# ThousandSunny.net
KiCad netlist of a schematic drawn in EAGLE
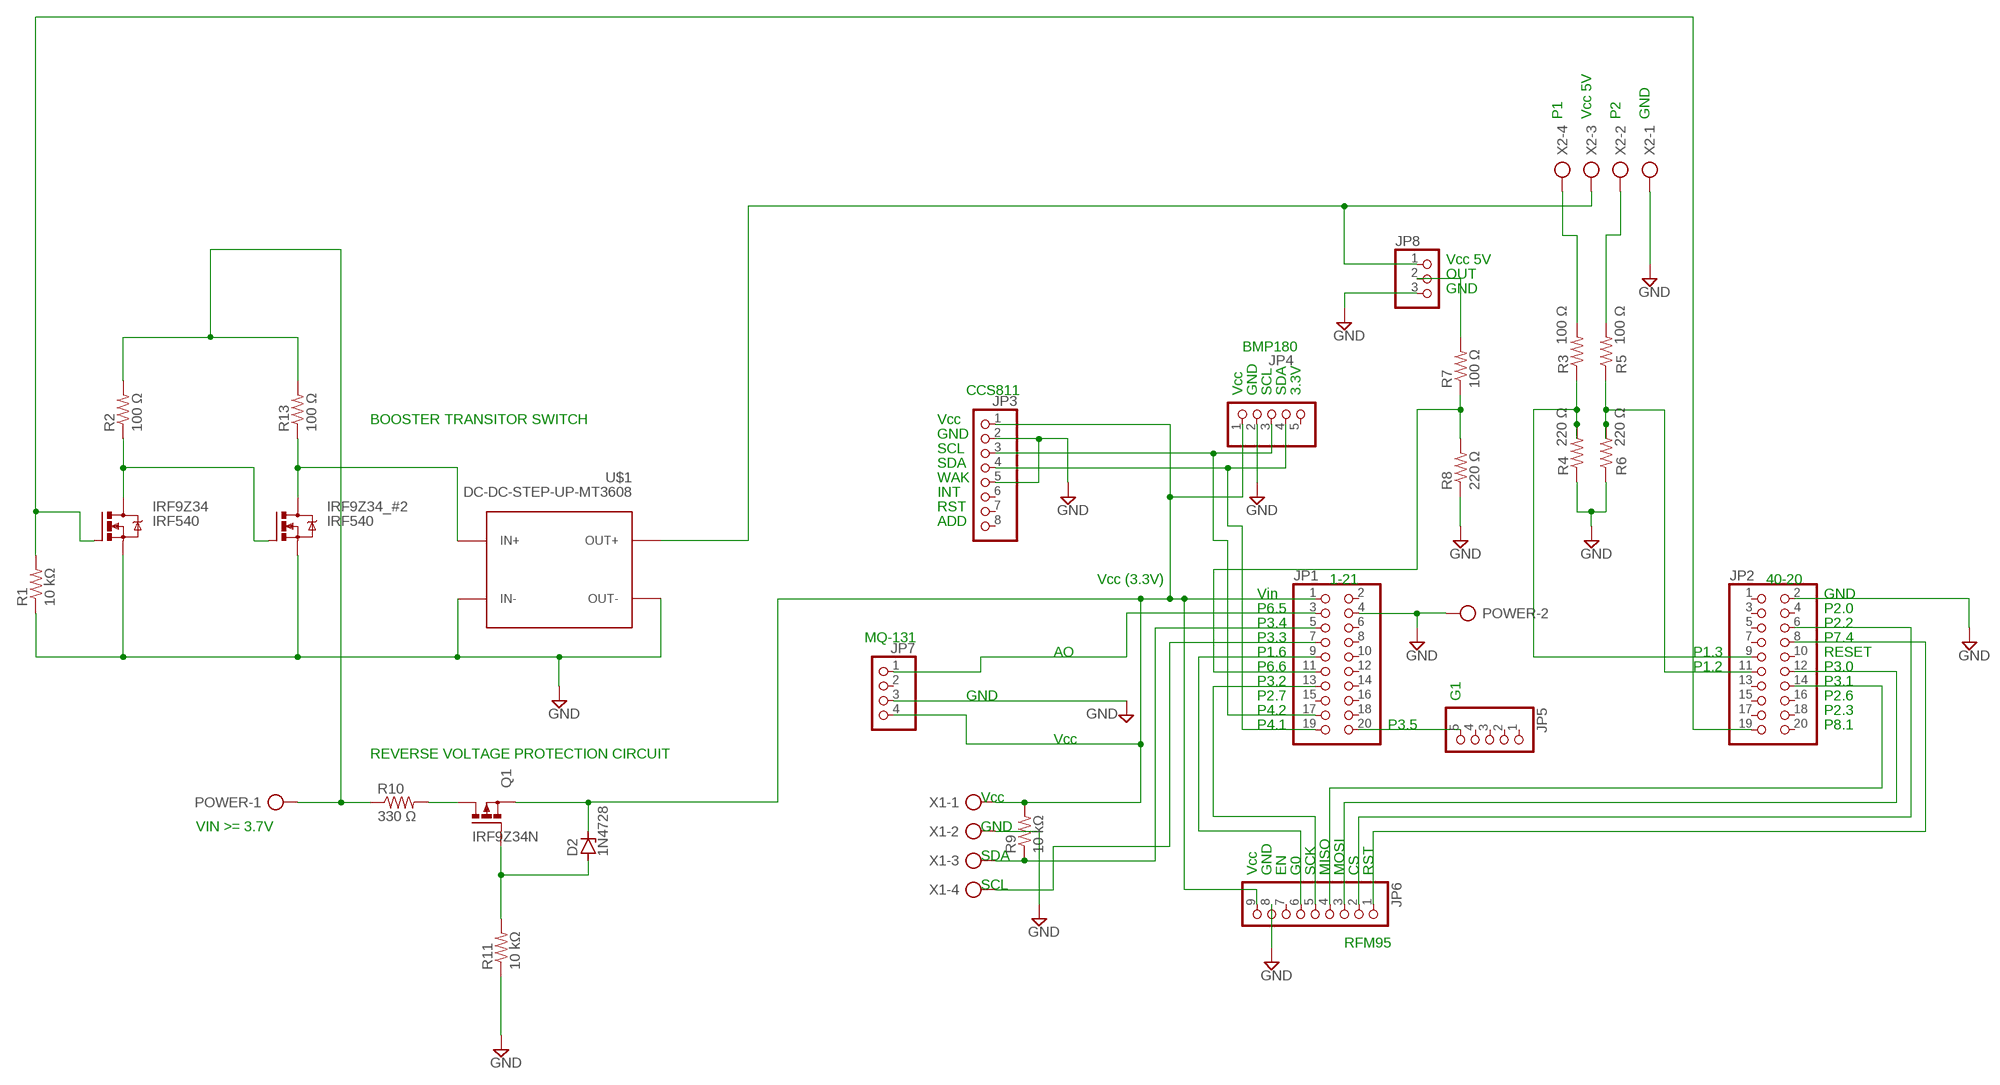
[diagram p0: schematic, sheet 1]

(export (version "E")
  (design (tool "Eeschema 10.0.6"))
  (components
    (comp (ref "D2")
      (value "1N4728")
      (footprint "eagle-import:DO41Z10")
      (libsource (lib "eagle-import") (part "1N4728"))
    )
    (comp (ref "IRF9Z34")
      (value "IRF540")
      (footprint "eagle-import:TO220BV")
      (libsource (lib "eagle-import") (part "IRF540"))
    )
    (comp (ref "IRF9Z34_#2")
      (value "IRF540")
      (footprint "eagle-import:TO220BV")
      (libsource (lib "eagle-import") (part "IRF540"))
    )
    (comp (ref "JP1")
      (value "PINHD-2X10")
      (footprint "eagle-import:2X10")
      (libsource (lib "eagle-import") (part "PINHD-2X10"))
    )
    (comp (ref "JP2")
      (value "PINHD-2X10")
      (footprint "eagle-import:2X10")
      (libsource (lib "eagle-import") (part "PINHD-2X10"))
    )
    (comp (ref "JP3")
      (value "PINHD-1X8")
      (footprint "eagle-import:1X08")
      (libsource (lib "eagle-import") (part "PINHD-1X8"))
    )
    (comp (ref "JP4")
      (value "PINHD-1X5")
      (footprint "eagle-import:1X05")
      (libsource (lib "eagle-import") (part "PINHD-1X5"))
    )
    (comp (ref "JP5")
      (value "PINHD-1X5")
      (footprint "eagle-import:1X05")
      (libsource (lib "eagle-import") (part "PINHD-1X5"))
    )
    (comp (ref "JP6")
      (value "PINHD-1X9")
      (footprint "eagle-import:1X09")
      (libsource (lib "eagle-import") (part "PINHD-1X9"))
    )
    (comp (ref "JP7")
      (value "PINHD-1X4")
      (footprint "eagle-import:1X04")
      (libsource (lib "eagle-import") (part "PINHD-1X4"))
    )
    (comp (ref "JP8")
      (value "PINHD-1X3")
      (footprint "eagle-import:1X03")
      (libsource (lib "eagle-import") (part "PINHD-1X3"))
    )
    (comp (ref "POWER")
      (value "AK300/2")
      (footprint "eagle-import:AK300_2")
      (libsource (lib "eagle-import") (part "AK300/2"))
    )
    (comp (ref "Q1")
      (value "IRF9Z34N")
      (footprint "eagle-import:TO220BV")
      (libsource (lib "eagle-import") (part "PMOSFET_PTO220BV"))
    )
    (comp (ref "R1")
      (value "10 kΩ")
      (footprint "eagle-import:0204_7")
      (libsource (lib "eagle-import") (part "R-US_0204/7"))
    )
    (comp (ref "R2")
      (value "100 Ω")
      (footprint "eagle-import:0204_7")
      (libsource (lib "eagle-import") (part "R-US_0204/7"))
    )
    (comp (ref "R3")
      (value "100 Ω")
      (footprint "eagle-import:0204_7")
      (libsource (lib "eagle-import") (part "R-US_0204/7"))
    )
    (comp (ref "R4")
      (value "220 Ω")
      (footprint "eagle-import:0204_7")
      (libsource (lib "eagle-import") (part "R-US_0204/7"))
    )
    (comp (ref "R5")
      (value "100 Ω")
      (footprint "eagle-import:0204_7")
      (libsource (lib "eagle-import") (part "R-US_0204/7"))
    )
    (comp (ref "R6")
      (value "220 Ω")
      (footprint "eagle-import:0204_7")
      (libsource (lib "eagle-import") (part "R-US_0204/7"))
    )
    (comp (ref "R7")
      (value "100 Ω")
      (footprint "eagle-import:0204_7")
      (libsource (lib "eagle-import") (part "R-US_0204/7"))
    )
    (comp (ref "R8")
      (value "220 Ω")
      (footprint "eagle-import:0204_7")
      (libsource (lib "eagle-import") (part "R-US_0204/7"))
    )
    (comp (ref "R9")
      (value "10 kΩ")
      (footprint "eagle-import:0204_7")
      (libsource (lib "eagle-import") (part "R-US_0204/7"))
    )
    (comp (ref "R10")
      (value "330 Ω")
      (footprint "eagle-import:0204_7")
      (libsource (lib "eagle-import") (part "R-US_0204/7"))
    )
    (comp (ref "R11")
      (value "10 kΩ")
      (footprint "eagle-import:0204_7")
      (libsource (lib "eagle-import") (part "R-US_0204/7"))
    )
    (comp (ref "R13")
      (value "100 Ω")
      (footprint "eagle-import:0204_7")
      (libsource (lib "eagle-import") (part "R-US_0204/7"))
    )
    (comp (ref "U$1")
      (value "DC-DC-STEP-UP-MT3608")
      (footprint "eagle-import:DC-DC-STEP-UP-MT3608")
      (libsource (lib "eagle-import") (part "DC-DC-STEP-UP-MT3608"))
    )
    (comp (ref "X1")
      (value "AK300/4")
      (footprint "eagle-import:AK300_4")
      (libsource (lib "eagle-import") (part "AK300/4"))
    )
    (comp (ref "X2")
      (value "AK300/4")
      (footprint "eagle-import:AK300_4")
      (libsource (lib "eagle-import") (part "AK300/4"))
    )
  )
  (nets
    (net (code "1") (name "GND") (class "Default")
      (node (ref "IRF9Z34") (pin "S") (pinfunction "S_S") (pintype "passive"))
      (node (ref "IRF9Z34_#2") (pin "S") (pinfunction "S_S") (pintype "passive"))
      (node (ref "JP1") (pin "4") (pinfunction "4_4") (pintype "passive"))
      (node (ref "JP2") (pin "2") (pinfunction "2_2") (pintype "passive"))
      (node (ref "JP3") (pin "2") (pinfunction "2_2") (pintype "passive"))
      (node (ref "JP3") (pin "5") (pinfunction "5_5") (pintype "passive"))
      (node (ref "JP4") (pin "2") (pinfunction "2_2") (pintype "passive"))
      (node (ref "JP6") (pin "8") (pinfunction "8_8") (pintype "passive"))
      (node (ref "JP7") (pin "3") (pinfunction "3_3") (pintype "passive"))
      (node (ref "JP8") (pin "3") (pinfunction "3_3") (pintype "passive"))
      (node (ref "POWER") (pin "2") (pinfunction "KL_2") (pintype "passive"))
      (node (ref "R1") (pin "1") (pinfunction "1_1") (pintype "passive"))
      (node (ref "R11") (pin "1") (pinfunction "1_1") (pintype "passive"))
      (node (ref "R4") (pin "1") (pinfunction "1_1") (pintype "passive"))
      (node (ref "R6") (pin "1") (pinfunction "1_1") (pintype "passive"))
      (node (ref "R8") (pin "1") (pinfunction "1_1") (pintype "passive"))
      (node (ref "U$1") (pin "IN-") (pinfunction "IN-_IN-") (pintype "bidirectional"))
      (node (ref "U$1") (pin "OUT-") (pinfunction "OUT-_OUT-") (pintype "bidirectional"))
      (node (ref "X1") (pin "2") (pinfunction "KL_2") (pintype "passive"))
      (node (ref "X2") (pin "1") (pinfunction "KL_1") (pintype "passive"))
    )
    (net (code "2") (name "Net-(D2-PadA)") (class "Default")
      (node (ref "D2") (pin "A") (pinfunction "A_A") (pintype "passive"))
      (node (ref "Q1") (pin "G") (pinfunction "G_G") (pintype "passive"))
      (node (ref "R11") (pin "2") (pinfunction "2_2") (pintype "passive"))
    )
    (net (code "3") (name "Net-(IRF9Z34-PadD)") (class "Default")
      (node (ref "IRF9Z34") (pin "D") (pinfunction "D_D") (pintype "passive"))
      (node (ref "IRF9Z34_#2") (pin "G") (pinfunction "G_G") (pintype "passive"))
      (node (ref "R2") (pin "1") (pinfunction "1_1") (pintype "passive"))
    )
    (net (code "4") (name "Net-(IRF9Z34-PadG)") (class "Default")
      (node (ref "IRF9Z34") (pin "G") (pinfunction "G_G") (pintype "passive"))
      (node (ref "JP2") (pin "19") (pinfunction "19_19") (pintype "passive"))
      (node (ref "R1") (pin "2") (pinfunction "2_2") (pintype "passive"))
    )
    (net (code "5") (name "Net-(IRF9Z34_#2-PadD)") (class "Default")
      (node (ref "IRF9Z34_#2") (pin "D") (pinfunction "D_D") (pintype "passive"))
      (node (ref "R13") (pin "1") (pinfunction "1_1") (pintype "passive"))
      (node (ref "U$1") (pin "IN+") (pinfunction "IN+_IN+") (pintype "bidirectional"))
    )
    (net (code "6") (name "Net-(JP1-Pad3)") (class "Default")
      (node (ref "JP1") (pin "3") (pinfunction "3_3") (pintype "passive"))
      (node (ref "JP7") (pin "1") (pinfunction "1_1") (pintype "passive"))
    )
    (net (code "7") (name "Net-(JP1-Pad9)") (class "Default")
      (node (ref "JP1") (pin "9") (pinfunction "9_9") (pintype "passive"))
      (node (ref "JP6") (pin "6") (pinfunction "6_6") (pintype "passive"))
    )
    (net (code "8") (name "Net-(JP1-Pad11)") (class "Default")
      (node (ref "JP1") (pin "11") (pinfunction "11_11") (pintype "passive"))
      (node (ref "R7") (pin "1") (pinfunction "1_1") (pintype "passive"))
      (node (ref "R8") (pin "2") (pinfunction "2_2") (pintype "passive"))
    )
    (net (code "9") (name "Net-(JP1-Pad13)") (class "Default")
      (node (ref "JP1") (pin "13") (pinfunction "13_13") (pintype "passive"))
      (node (ref "JP6") (pin "5") (pinfunction "5_5") (pintype "passive"))
    )
    (net (code "10") (name "Net-(JP1-Pad17)") (class "Default")
      (node (ref "JP1") (pin "17") (pinfunction "17_17") (pintype "passive"))
      (node (ref "JP3") (pin "3") (pinfunction "3_3") (pintype "passive"))
      (node (ref "JP4") (pin "3") (pinfunction "3_3") (pintype "passive"))
    )
    (net (code "11") (name "Net-(JP1-Pad19)") (class "Default")
      (node (ref "JP1") (pin "19") (pinfunction "19_19") (pintype "passive"))
      (node (ref "JP3") (pin "4") (pinfunction "4_4") (pintype "passive"))
      (node (ref "JP4") (pin "4") (pinfunction "4_4") (pintype "passive"))
    )
    (net (code "12") (name "Net-(JP1-Pad20)") (class "Default")
      (node (ref "JP1") (pin "20") (pinfunction "20_20") (pintype "passive"))
      (node (ref "JP5") (pin "5") (pinfunction "5_5") (pintype "passive"))
    )
    (net (code "13") (name "Net-(JP2-Pad6)") (class "Default")
      (node (ref "JP2") (pin "6") (pinfunction "6_6") (pintype "passive"))
      (node (ref "JP6") (pin "2") (pinfunction "2_2") (pintype "passive"))
    )
    (net (code "14") (name "Net-(JP2-Pad8)") (class "Default")
      (node (ref "JP2") (pin "8") (pinfunction "8_8") (pintype "passive"))
      (node (ref "JP6") (pin "1") (pinfunction "1_1") (pintype "passive"))
    )
    (net (code "15") (name "Net-(JP2-Pad9)") (class "Default")
      (node (ref "JP2") (pin "9") (pinfunction "9_9") (pintype "passive"))
      (node (ref "R3") (pin "1") (pinfunction "1_1") (pintype "passive"))
      (node (ref "R4") (pin "2") (pinfunction "2_2") (pintype "passive"))
    )
    (net (code "16") (name "Net-(JP2-Pad11)") (class "Default")
      (node (ref "JP2") (pin "11") (pinfunction "11_11") (pintype "passive"))
      (node (ref "R5") (pin "1") (pinfunction "1_1") (pintype "passive"))
      (node (ref "R6") (pin "2") (pinfunction "2_2") (pintype "passive"))
    )
    (net (code "17") (name "Net-(JP2-Pad12)") (class "Default")
      (node (ref "JP2") (pin "12") (pinfunction "12_12") (pintype "passive"))
      (node (ref "JP6") (pin "3") (pinfunction "3_3") (pintype "passive"))
    )
    (net (code "18") (name "Net-(JP2-Pad14)") (class "Default")
      (node (ref "JP2") (pin "14") (pinfunction "14_14") (pintype "passive"))
      (node (ref "JP6") (pin "4") (pinfunction "4_4") (pintype "passive"))
    )
    (net (code "19") (name "Net-(JP8-Pad2)") (class "Default")
      (node (ref "JP8") (pin "2") (pinfunction "2_2") (pintype "passive"))
      (node (ref "R7") (pin "2") (pinfunction "2_2") (pintype "passive"))
    )
    (net (code "20") (name "Net-(POWERA-KL)") (class "Default")
      (node (ref "POWER") (pin "1") (pinfunction "KL_1") (pintype "passive"))
      (node (ref "R10") (pin "1") (pinfunction "1_1") (pintype "passive"))
      (node (ref "R13") (pin "2") (pinfunction "2_2") (pintype "passive"))
      (node (ref "R2") (pin "2") (pinfunction "2_2") (pintype "passive"))
    )
    (net (code "21") (name "Net-(Q1-PadD)") (class "Default")
      (node (ref "Q1") (pin "D") (pinfunction "D_D") (pintype "passive"))
      (node (ref "R10") (pin "2") (pinfunction "2_2") (pintype "passive"))
    )
    (net (code "22") (name "Net-(X1A-KL)") (class "Default")
      (node (ref "D2") (pin "C") (pinfunction "C_C") (pintype "passive"))
      (node (ref "JP1") (pin "1") (pinfunction "1_1") (pintype "passive"))
      (node (ref "JP3") (pin "1") (pinfunction "1_1") (pintype "passive"))
      (node (ref "JP4") (pin "1") (pinfunction "1_1") (pintype "passive"))
      (node (ref "JP6") (pin "9") (pinfunction "9_9") (pintype "passive"))
      (node (ref "JP7") (pin "4") (pinfunction "4_4") (pintype "passive"))
      (node (ref "Q1") (pin "S") (pinfunction "S_S") (pintype "passive"))
      (node (ref "R9") (pin "2") (pinfunction "2_2") (pintype "passive"))
      (node (ref "X1") (pin "1") (pinfunction "KL_1") (pintype "passive"))
    )
    (net (code "23") (name "Net-(X1C-KL)") (class "Default")
      (node (ref "JP1") (pin "5") (pinfunction "5_5") (pintype "passive"))
      (node (ref "R9") (pin "1") (pinfunction "1_1") (pintype "passive"))
      (node (ref "X1") (pin "3") (pinfunction "KL_3") (pintype "passive"))
    )
    (net (code "24") (name "Net-(X1D-KL)") (class "Default")
      (node (ref "JP1") (pin "7") (pinfunction "7_7") (pintype "passive"))
      (node (ref "X1") (pin "4") (pinfunction "KL_4") (pintype "passive"))
    )
    (net (code "25") (name "Net-(X2B-KL)") (class "Default")
      (node (ref "R5") (pin "2") (pinfunction "2_2") (pintype "passive"))
      (node (ref "X2") (pin "2") (pinfunction "KL_2") (pintype "passive"))
    )
    (net (code "26") (name "Net-(X2C-KL)") (class "Default")
      (node (ref "JP8") (pin "1") (pinfunction "1_1") (pintype "passive"))
      (node (ref "U$1") (pin "OUT+") (pinfunction "OUT+_OUT+") (pintype "bidirectional"))
      (node (ref "X2") (pin "3") (pinfunction "KL_3") (pintype "passive"))
    )
    (net (code "27") (name "Net-(X2D-KL)") (class "Default")
      (node (ref "R3") (pin "2") (pinfunction "2_2") (pintype "passive"))
      (node (ref "X2") (pin "4") (pinfunction "KL_4") (pintype "passive"))
    )
    (net (code "28") (name "unconnected-(JP1-Pad2)") (class "Default")
      (node (ref "JP1") (pin "2") (pinfunction "2_2") (pintype "passive"))
    )
    (net (code "29") (name "unconnected-(JP1-Pad6)") (class "Default")
      (node (ref "JP1") (pin "6") (pinfunction "6_6") (pintype "passive"))
    )
    (net (code "30") (name "unconnected-(JP1-Pad8)") (class "Default")
      (node (ref "JP1") (pin "8") (pinfunction "8_8") (pintype "passive"))
    )
    (net (code "31") (name "unconnected-(JP1-Pad10)") (class "Default")
      (node (ref "JP1") (pin "10") (pinfunction "10_10") (pintype "passive"))
    )
    (net (code "32") (name "unconnected-(JP1-Pad12)") (class "Default")
      (node (ref "JP1") (pin "12") (pinfunction "12_12") (pintype "passive"))
    )
    (net (code "33") (name "unconnected-(JP1-Pad14)") (class "Default")
      (node (ref "JP1") (pin "14") (pinfunction "14_14") (pintype "passive"))
    )
    (net (code "34") (name "unconnected-(JP1-Pad15)") (class "Default")
      (node (ref "JP1") (pin "15") (pinfunction "15_15") (pintype "passive"))
    )
    (net (code "35") (name "unconnected-(JP1-Pad16)") (class "Default")
      (node (ref "JP1") (pin "16") (pinfunction "16_16") (pintype "passive"))
    )
    (net (code "36") (name "unconnected-(JP1-Pad18)") (class "Default")
      (node (ref "JP1") (pin "18") (pinfunction "18_18") (pintype "passive"))
    )
    (net (code "37") (name "unconnected-(JP2-Pad1)") (class "Default")
      (node (ref "JP2") (pin "1") (pinfunction "1_1") (pintype "passive"))
    )
    (net (code "38") (name "unconnected-(JP2-Pad3)") (class "Default")
      (node (ref "JP2") (pin "3") (pinfunction "3_3") (pintype "passive"))
    )
    (net (code "39") (name "unconnected-(JP2-Pad4)") (class "Default")
      (node (ref "JP2") (pin "4") (pinfunction "4_4") (pintype "passive"))
    )
    (net (code "40") (name "unconnected-(JP2-Pad5)") (class "Default")
      (node (ref "JP2") (pin "5") (pinfunction "5_5") (pintype "passive"))
    )
    (net (code "41") (name "unconnected-(JP2-Pad7)") (class "Default")
      (node (ref "JP2") (pin "7") (pinfunction "7_7") (pintype "passive"))
    )
    (net (code "42") (name "unconnected-(JP2-Pad10)") (class "Default")
      (node (ref "JP2") (pin "10") (pinfunction "10_10") (pintype "passive"))
    )
    (net (code "43") (name "unconnected-(JP2-Pad13)") (class "Default")
      (node (ref "JP2") (pin "13") (pinfunction "13_13") (pintype "passive"))
    )
    (net (code "44") (name "unconnected-(JP2-Pad15)") (class "Default")
      (node (ref "JP2") (pin "15") (pinfunction "15_15") (pintype "passive"))
    )
    (net (code "45") (name "unconnected-(JP2-Pad16)") (class "Default")
      (node (ref "JP2") (pin "16") (pinfunction "16_16") (pintype "passive"))
    )
    (net (code "46") (name "unconnected-(JP2-Pad17)") (class "Default")
      (node (ref "JP2") (pin "17") (pinfunction "17_17") (pintype "passive"))
    )
    (net (code "47") (name "unconnected-(JP2-Pad18)") (class "Default")
      (node (ref "JP2") (pin "18") (pinfunction "18_18") (pintype "passive"))
    )
    (net (code "48") (name "unconnected-(JP2-Pad20)") (class "Default")
      (node (ref "JP2") (pin "20") (pinfunction "20_20") (pintype "passive"))
    )
    (net (code "49") (name "unconnected-(JP3-Pad6)") (class "Default")
      (node (ref "JP3") (pin "6") (pinfunction "6_6") (pintype "passive"))
    )
    (net (code "50") (name "unconnected-(JP3-Pad7)") (class "Default")
      (node (ref "JP3") (pin "7") (pinfunction "7_7") (pintype "passive"))
    )
    (net (code "51") (name "unconnected-(JP3-Pad8)") (class "Default")
      (node (ref "JP3") (pin "8") (pinfunction "8_8") (pintype "passive"))
    )
    (net (code "52") (name "unconnected-(JP4-Pad5)") (class "Default")
      (node (ref "JP4") (pin "5") (pinfunction "5_5") (pintype "passive"))
    )
    (net (code "53") (name "unconnected-(JP5-Pad1)") (class "Default")
      (node (ref "JP5") (pin "1") (pinfunction "1_1") (pintype "passive"))
    )
    (net (code "54") (name "unconnected-(JP5-Pad2)") (class "Default")
      (node (ref "JP5") (pin "2") (pinfunction "2_2") (pintype "passive"))
    )
    (net (code "55") (name "unconnected-(JP5-Pad3)") (class "Default")
      (node (ref "JP5") (pin "3") (pinfunction "3_3") (pintype "passive"))
    )
    (net (code "56") (name "unconnected-(JP5-Pad4)") (class "Default")
      (node (ref "JP5") (pin "4") (pinfunction "4_4") (pintype "passive"))
    )
    (net (code "57") (name "unconnected-(JP6-Pad7)") (class "Default")
      (node (ref "JP6") (pin "7") (pinfunction "7_7") (pintype "passive"))
    )
    (net (code "58") (name "unconnected-(JP7-Pad2)") (class "Default")
      (node (ref "JP7") (pin "2") (pinfunction "2_2") (pintype "passive"))
    )
  )
)
